# Sheet3.net
KiCad netlist of a schematic drawn in Altium Designer
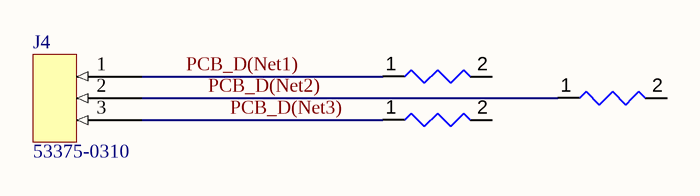
[diagram p0: Sheet3.SchDoc]

(export (version "E")
  (design (tool "Eeschema 10.0.6"))
  (components
    (comp (ref "J4")
      (value "53375-0310")
      (footprint "PCB1:SOJ127P870X356-20M")
      (fields (field (name "MANUFACTURER") "Molex"))
      (libsource (lib "SCH") (part "CMP-002-00074-2"))
    )
    (comp (ref "R1")
      (value "Resistor 10k +/-1% 1206 250 mW")
      (footprint "RESC3216X60X45ML15T20")
      (description "Chip Resistor, 10 KOhm, +/- 1%, 0.25 W, -55 to 155 degC, 1206 (3216 Metric)")
      (fields (field (name "TOLERANCE") "1%") (field (name "POWER") "250mW"))
      (libsource (lib "SCH") (part "RES-2"))
    )
    (comp (ref "R2")
      (value "Resistor 10k +/-1% 1206 250 mW")
      (footprint "RESC3216X60X45ML15T20")
      (description "Chip Resistor, 10 KOhm, +/- 1%, 0.25 W, -55 to 155 degC, 1206 (3216 Metric)")
      (fields (field (name "TOLERANCE") "1%") (field (name "POWER") "250mW"))
      (libsource (lib "SCH") (part "RES-2"))
    )
    (comp (ref "R3")
      (value "Resistor 10k +/-1% 1206 250 mW")
      (footprint "RESC3216X60X45ML15T20")
      (description "Chip Resistor, 10 KOhm, +/- 1%, 0.25 W, -55 to 155 degC, 1206 (3216 Metric)")
      (fields (field (name "TOLERANCE") "1%") (field (name "POWER") "250mW"))
      (libsource (lib "SCH") (part "RES-2"))
    )
  )
  (nets
    (net (code "1") (name "/PCB_D(Net1)") (class "Default")
      (node (ref "J4") (pin "1") (pinfunction "1_1") (pintype "input"))
      (node (ref "R1") (pin "1") (pinfunction "1_1") (pintype "passive"))
    )
    (net (code "2") (name "/PCB_D(Net2)") (class "Default")
      (node (ref "J4") (pin "2") (pinfunction "2_2") (pintype "input"))
      (node (ref "R2") (pin "1") (pinfunction "1_1") (pintype "passive"))
    )
    (net (code "3") (name "/PCB_D(Net3)") (class "Default")
      (node (ref "J4") (pin "3") (pinfunction "3_3") (pintype "input"))
      (node (ref "R3") (pin "1") (pinfunction "1_1") (pintype "passive"))
    )
    (net (code "4") (name "unconnected-(R1-Pad2)") (class "Default")
      (node (ref "R1") (pin "2") (pinfunction "2_2") (pintype "passive"))
    )
    (net (code "5") (name "unconnected-(R2-Pad2)") (class "Default")
      (node (ref "R2") (pin "2") (pinfunction "2_2") (pintype "passive"))
    )
    (net (code "6") (name "unconnected-(R3-Pad2)") (class "Default")
      (node (ref "R3") (pin "2") (pinfunction "2_2") (pintype "passive"))
    )
  )
)
